# ModuleDieuKhienNguoiDung.net
KiCad netlist of a schematic drawn in Altium Designer
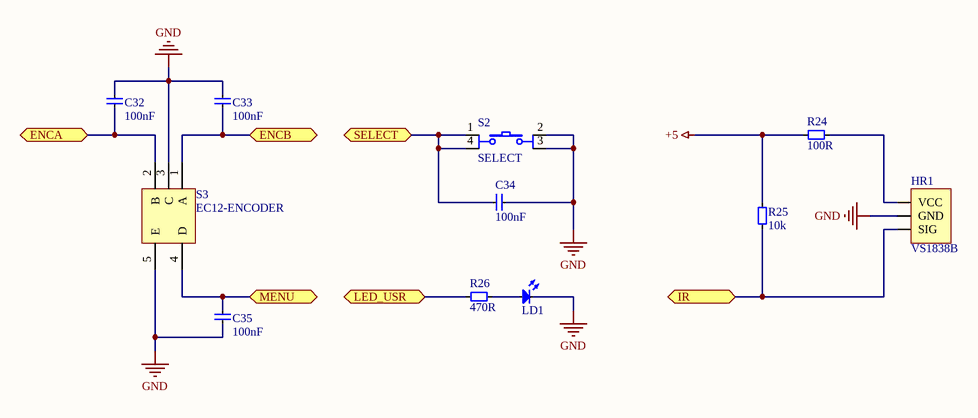
[diagram p0: ModuleDieuKhienNguoiDung.SchDoc]

(export (version "E")
  (design (tool "Eeschema 10.0.6"))
  (components
    (comp (ref "C32")
      (value "100nF")
      (footprint "C-0805")
      (description "Cac Loai Tu Khong Phan Cuc")
      (libsource (lib "phatvu1294_Lib") (part "CAP"))
    )
    (comp (ref "C33")
      (value "100nF")
      (footprint "C-0805")
      (description "Cac Loai Tu Khong Phan Cuc")
      (libsource (lib "phatvu1294_Lib") (part "CAP"))
    )
    (comp (ref "C34")
      (value "100nF")
      (footprint "C-0805")
      (description "Cac Loai Tu Khong Phan Cuc")
      (libsource (lib "phatvu1294_Lib") (part "CAP"))
    )
    (comp (ref "C35")
      (value "100nF")
      (footprint "C-0805")
      (description "Cac Loai Tu Khong Phan Cuc")
      (libsource (lib "phatvu1294_Lib") (part "CAP"))
    )
    (comp (ref "HR1")
      (value "VS1838B")
      (footprint "VS1838B-A")
      (description "Module Giai Ma IR")
      (libsource (lib "phatvu1294_Lib") (part "VS1838B"))
    )
    (comp (ref "LD1")
      (value "USR")
      (footprint "LED-0805-RED")
      (description "Cac Loai LED Don")
      (libsource (lib "phatvu1294_Lib") (part "LED"))
    )
    (comp (ref "R24")
      (value "100R")
      (footprint "R-0805")
      (description "Cac Loai Dien Tro")
      (libsource (lib "phatvu1294_Lib") (part "RES"))
    )
    (comp (ref "R25")
      (value "10k")
      (footprint "R-0805")
      (description "Cac Loai Dien Tro")
      (libsource (lib "phatvu1294_Lib") (part "RES"))
    )
    (comp (ref "R26")
      (value "470R")
      (footprint "R-0805")
      (description "Cac Loai Dien Tro")
      (libsource (lib "phatvu1294_Lib") (part "RES"))
    )
    (comp (ref "S2")
      (value "SELECT")
      (footprint "SW4P-DIP-6X6MM")
      (description "Nut Nhan 4 Chan 6X6MM")
      (libsource (lib "phatvu1294_Lib") (part "SW4P-DIP-6X6MM"))
    )
    (comp (ref "S3")
      (value "EC12-ENCODER")
      (footprint "EC12-ENCODER")
      (description "Encoder Xoay Vo Cap Co Nut Nhan")
      (libsource (lib "Switch") (part "EC12-ENCODER"))
    )
  )
  (nets
    (net (code "1") (name "+5") (class "Default")
      (node (ref "R24") (pin "2") (pinfunction "2_2") (pintype "passive"))
      (node (ref "R25") (pin "2") (pinfunction "2_2") (pintype "passive"))
    )
    (net (code "2") (name "/ENCA") (class "Default")
      (node (ref "C32") (pin "1") (pinfunction "1_1") (pintype "passive"))
      (node (ref "S3") (pin "2") (pinfunction "B_2") (pintype "passive"))
    )
    (net (code "3") (name "/ENCB") (class "Default")
      (node (ref "C33") (pin "1") (pinfunction "1_1") (pintype "passive"))
      (node (ref "S3") (pin "1") (pinfunction "A_1") (pintype "passive"))
    )
    (net (code "4") (name "/IR") (class "Default")
      (node (ref "HR1") (pin "1") (pinfunction "SIG_1") (pintype "passive"))
      (node (ref "R25") (pin "1") (pinfunction "1_1") (pintype "passive"))
    )
    (net (code "5") (name "/LED_USR") (class "Default")
      (node (ref "R26") (pin "1") (pinfunction "1_1") (pintype "passive"))
    )
    (net (code "6") (name "/MENU") (class "Default")
      (node (ref "C35") (pin "1") (pinfunction "1_1") (pintype "passive"))
      (node (ref "S3") (pin "4") (pinfunction "D_4") (pintype "passive"))
    )
    (net (code "7") (name "/SELECT") (class "Default")
      (node (ref "C34") (pin "1") (pinfunction "1_1") (pintype "passive"))
      (node (ref "S2") (pin "1") (pinfunction "1_1") (pintype "passive"))
      (node (ref "S2") (pin "4") (pinfunction "4_4") (pintype "passive"))
    )
    (net (code "8") (name "GND") (class "Default")
      (node (ref "C32") (pin "2") (pinfunction "2_2") (pintype "passive"))
      (node (ref "C33") (pin "2") (pinfunction "2_2") (pintype "passive"))
      (node (ref "C34") (pin "2") (pinfunction "2_2") (pintype "passive"))
      (node (ref "C35") (pin "2") (pinfunction "2_2") (pintype "passive"))
      (node (ref "HR1") (pin "2") (pinfunction "GND_2") (pintype "passive"))
      (node (ref "LD1") (pin "2") (pinfunction "2_2") (pintype "passive"))
      (node (ref "S2") (pin "2") (pinfunction "2_2") (pintype "passive"))
      (node (ref "S2") (pin "3") (pinfunction "3_3") (pintype "passive"))
      (node (ref "S3") (pin "3") (pinfunction "C_3") (pintype "passive"))
      (node (ref "S3") (pin "5") (pinfunction "E_5") (pintype "passive"))
    )
    (net (code "9") (name "Net-(HR1-VCC)") (class "Default")
      (node (ref "HR1") (pin "3") (pinfunction "VCC_3") (pintype "passive"))
      (node (ref "R24") (pin "1") (pinfunction "1_1") (pintype "passive"))
    )
    (net (code "10") (name "Net-(LD1-Pad1)") (class "Default")
      (node (ref "LD1") (pin "1") (pinfunction "1_1") (pintype "passive"))
      (node (ref "R26") (pin "2") (pinfunction "2_2") (pintype "passive"))
    )
  )
)
